# TMC2130-Eval_v13.net
KiCad netlist of a schematic drawn in EAGLE
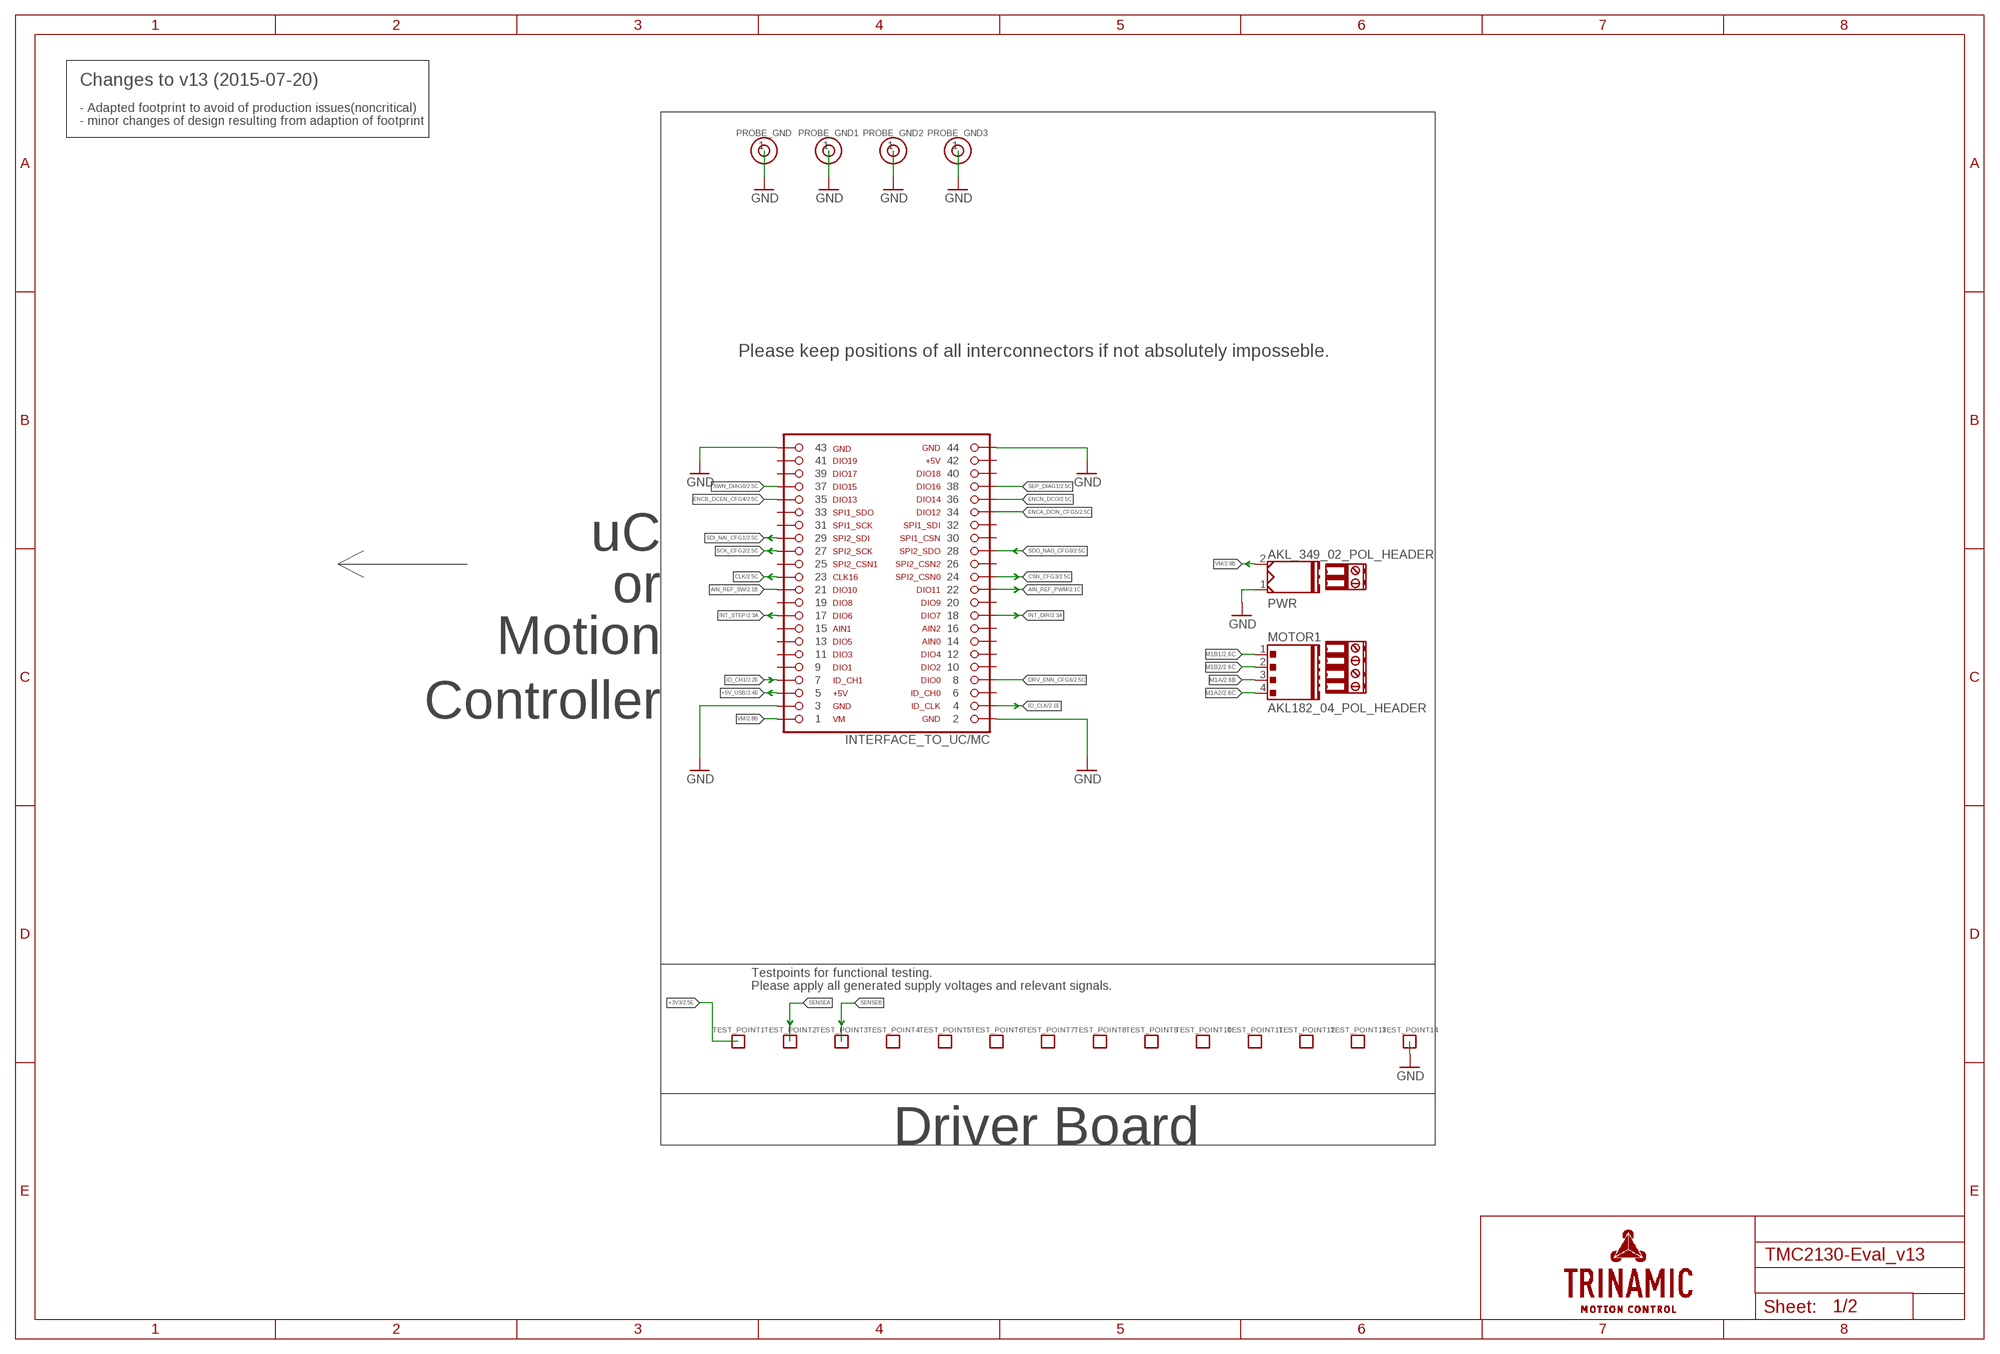
[diagram p0: schematic, sheet 1]
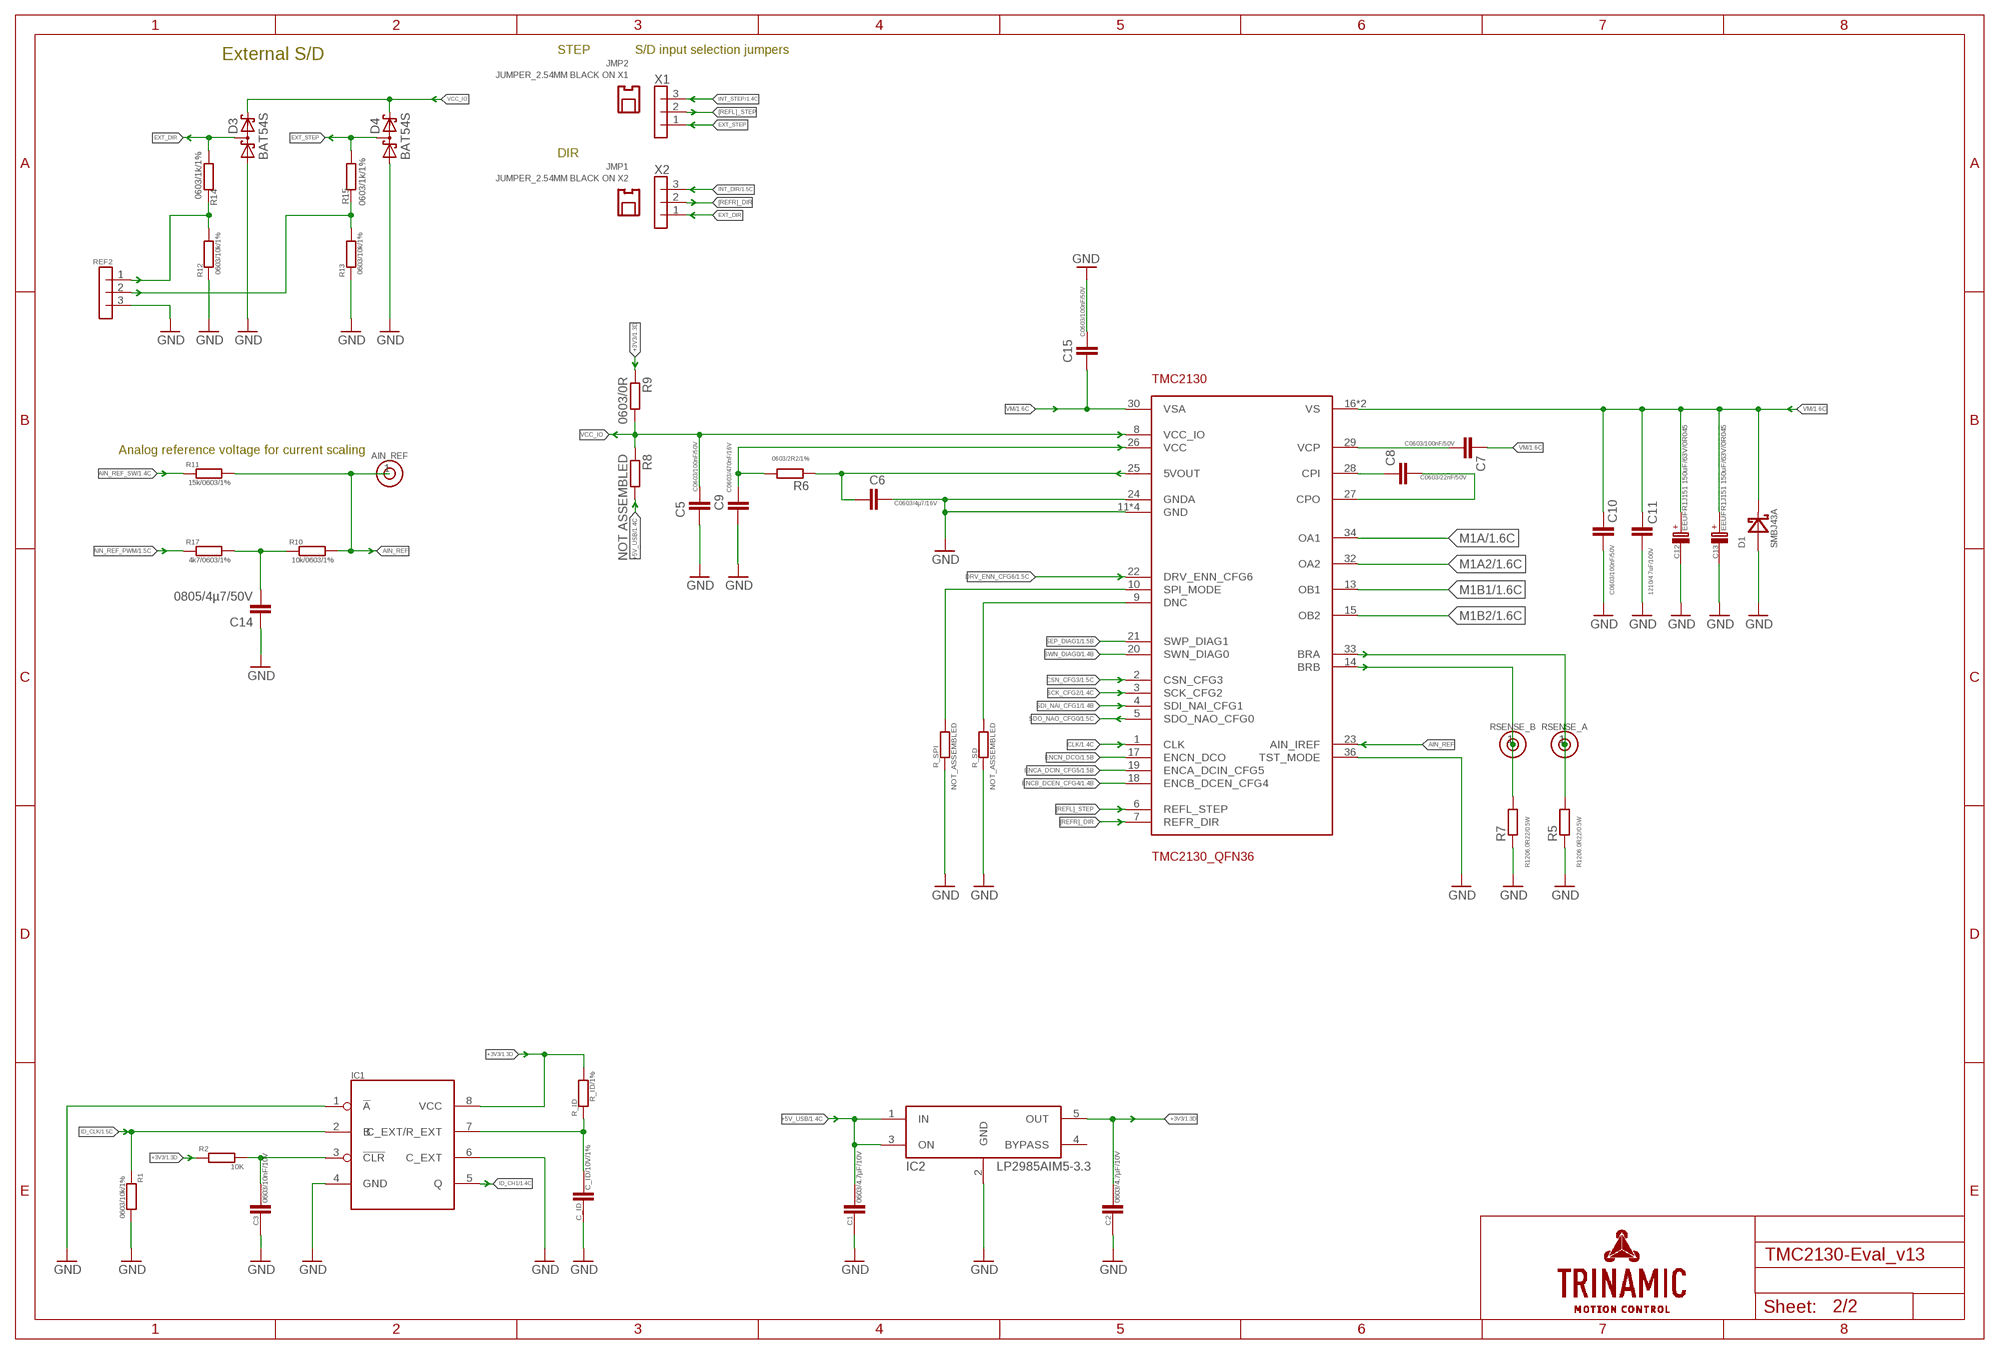
[diagram p1: schematic, sheet 2]

(export (version "E")
  (design (tool "Eeschema 10.0.6"))
  (components
    (comp (ref "INTERFACE_TO_UC/MC")
      (value "FEMALE_HEADER_SMD_2.54_44_PINSHORTPADS_HOLES")
      (footprint "eagle-import:FEMALE_HEADER_SMD_254_44_PIN_SHORTPADS_HOLES")
      (fields
        (field (name "1_PARTNUMBER") "098-3-044-1-NFX-YT0  ")
        (field (name "2_PARTNUMBER") "HLE-122-02-F-DV-A")
        (field (name "2_PARTNUMBER_1") "HLE-122-02-F-DV-A")
      )
      (libsource (lib "eagle-import") (part "FEMALE_HEADER_SMD_2.54_44_PINSHORTPADS_HOLES"))
    )
    (comp (ref "MOTOR1")
      (value "AKL182_04_POL_HEADER")
      (footprint "eagle-import:AKL169_04_POL")
      (fields (field (name "1_PARTNUMBER") "31182104") (field (name "2_PARTNUMBER") "AKL 182-04"))
      (libsource (lib "eagle-import") (part "AKL182_04_POL_HEADER"))
    )
    (comp (ref "PROBE_GND")
      (value "NOT ASSEMBLED")
      (footprint "eagle-import:1PIN_1ROW_THT")
      (libsource (lib "eagle-import") (part "1PIN_1ROW"))
    )
    (comp (ref "PROBE_GND1")
      (value "NOT ASSEMBLED")
      (footprint "eagle-import:1PIN_1ROW_THT")
      (libsource (lib "eagle-import") (part "1PIN_1ROW"))
    )
    (comp (ref "PROBE_GND2")
      (value "NOT ASSEMBLED")
      (footprint "eagle-import:1PIN_1ROW_THT")
      (libsource (lib "eagle-import") (part "1PIN_1ROW"))
    )
    (comp (ref "PROBE_GND3")
      (value "NOT ASSEMBLED")
      (footprint "eagle-import:1PIN_1ROW_THT")
      (libsource (lib "eagle-import") (part "1PIN_1ROW"))
    )
    (comp (ref "PWR")
      (value "AKL_349_02_POL_HEADER")
      (footprint "eagle-import:AKL349_02_POL")
      (fields (field (name "1_PARTNUMBER") "31330102") (field (name "2_PARTNUMBER") "AKL 330-02"))
      (libsource (lib "eagle-import") (part "AKL_349_02_POL_HEADER"))
    )
    (comp (ref "TERM1")
      (value "AKL_330_2_POL_TERMINAL")
      (footprint "eagle-import:EXTRA_TERMINAL")
      (fields (field (name "1_PARTNUMBER") "31349102") (field (name "2_PARTNUMBER") "AKL 349-02"))
      (libsource (lib "eagle-import") (part "AKL_330_2_POL_TERMINAL"))
    )
    (comp (ref "TERM2")
      (value "AKL182_04_POL_TERMINAL")
      (footprint "eagle-import:EXTRA_TERMINAL")
      (fields (field (name "1_PARTNUMBER") "31169104") (field (name "2_PARTNUMBER") "AKL 169-04"))
      (libsource (lib "eagle-import") (part "AKL182_04_POL_TERMINAL"))
    )
    (comp (ref "TEST_POINT1")
      (value "NOT ASSEMBLED")
      (footprint "eagle-import:PAD_R1.2")
      (libsource (lib "eagle-import") (part "PAD_ROUND"))
    )
    (comp (ref "TEST_POINT2")
      (value "NOT ASSEMBLED")
      (footprint "eagle-import:PAD_R1.2")
      (libsource (lib "eagle-import") (part "PAD_ROUND"))
    )
    (comp (ref "TEST_POINT3")
      (value "NOT ASSEMBLED")
      (footprint "eagle-import:PAD_R1.2")
      (libsource (lib "eagle-import") (part "PAD_ROUND"))
    )
    (comp (ref "TEST_POINT4")
      (value "NOT ASSEMBLED")
      (footprint "eagle-import:PAD_R1.2")
      (libsource (lib "eagle-import") (part "PAD_ROUND"))
    )
    (comp (ref "TEST_POINT5")
      (value "NOT ASSEMBLED")
      (footprint "eagle-import:PAD_R1.2")
      (libsource (lib "eagle-import") (part "PAD_ROUND"))
    )
    (comp (ref "TEST_POINT6")
      (value "NOT ASSEMBLED")
      (footprint "eagle-import:PAD_R1.2")
      (libsource (lib "eagle-import") (part "PAD_ROUND"))
    )
    (comp (ref "TEST_POINT7")
      (value "NOT ASSEMBLED")
      (footprint "eagle-import:PAD_R1.2")
      (libsource (lib "eagle-import") (part "PAD_ROUND"))
    )
    (comp (ref "TEST_POINT8")
      (value "NOT ASSEMBLED")
      (footprint "eagle-import:PAD_R1.2")
      (libsource (lib "eagle-import") (part "PAD_ROUND"))
    )
    (comp (ref "TEST_POINT9")
      (value "NOT ASSEMBLED")
      (footprint "eagle-import:PAD_R1.2")
      (libsource (lib "eagle-import") (part "PAD_ROUND"))
    )
    (comp (ref "TEST_POINT10")
      (value "NOT ASSEMBLED")
      (footprint "eagle-import:PAD_R1.2")
      (libsource (lib "eagle-import") (part "PAD_ROUND"))
    )
    (comp (ref "TEST_POINT11")
      (value "NOT ASSEMBLED")
      (footprint "eagle-import:PAD_R1.2")
      (libsource (lib "eagle-import") (part "PAD_ROUND"))
    )
    (comp (ref "TEST_POINT12")
      (value "NOT ASSEMBLED")
      (footprint "eagle-import:PAD_R1.2")
      (libsource (lib "eagle-import") (part "PAD_ROUND"))
    )
    (comp (ref "TEST_POINT13")
      (value "NOT ASSEMBLED")
      (footprint "eagle-import:PAD_R1.2")
      (libsource (lib "eagle-import") (part "PAD_ROUND"))
    )
    (comp (ref "TEST_POINT14")
      (value "NOT ASSEMBLED")
      (footprint "eagle-import:PAD_R1.2")
      (libsource (lib "eagle-import") (part "PAD_ROUND"))
    )
    (comp (ref "AIN_REF")
      (value "NOT ASSEMBLED")
      (footprint "eagle-import:1PIN_1ROW_THT")
      (libsource (lib "eagle-import") (part "1PIN_1ROW"))
    )
    (comp (ref "C1")
      (value "0603/4.7µF/10V")
      (footprint "eagle-import:RCL_0603")
      (libsource (lib "eagle-import") (part "RCL_C/0603"))
    )
    (comp (ref "C2")
      (value "0603/4.7µF/10V")
      (footprint "eagle-import:RCL_0603")
      (libsource (lib "eagle-import") (part "RCL_C/0603"))
    )
    (comp (ref "C3")
      (value "0603/10nF/10V")
      (footprint "eagle-import:RCL_0603")
      (libsource (lib "eagle-import") (part "RCL_C/0603"))
    )
    (comp (ref "C5")
      (value "C0603/100nF/50V")
      (footprint "eagle-import:C0603")
      (libsource (lib "eagle-import") (part "C-EUC0603"))
    )
    (comp (ref "C6")
      (value "C0603/4µ7/16V")
      (footprint "eagle-import:C0603")
      (libsource (lib "eagle-import") (part "C-EUC0603"))
    )
    (comp (ref "C7")
      (value "C0603/100nF/50V")
      (footprint "eagle-import:C0603")
      (libsource (lib "eagle-import") (part "C-EUC0603"))
    )
    (comp (ref "C8")
      (value "C0603/22nF/50V")
      (footprint "eagle-import:C0603")
      (libsource (lib "eagle-import") (part "C-EUC0603"))
    )
    (comp (ref "C9")
      (value "C0603/470nF/16V")
      (footprint "eagle-import:C0603")
      (libsource (lib "eagle-import") (part "C-EUC0603"))
    )
    (comp (ref "C10")
      (value "C0603/100nF/50V")
      (footprint "eagle-import:C0603")
      (libsource (lib "eagle-import") (part "C-EUC0603"))
    )
    (comp (ref "C11")
      (value "1210/4.7uF/100V")
      (footprint "eagle-import:C1210")
      (libsource (lib "eagle-import") (part "C-EUC1210"))
    )
    (comp (ref "C12")
      (value "EEUFR1J151 150uF/63V/0R045")
      (footprint "eagle-import:C_POL_RAD_THT_5X10X12.5")
      (libsource (lib "eagle-import") (part "C_POL"))
    )
    (comp (ref "C13")
      (value "EEUFR1J151 150uF/63V/0R045")
      (footprint "eagle-import:C_POL_RAD_THT_5X10X12.5")
      (libsource (lib "eagle-import") (part "C_POL"))
    )
    (comp (ref "C14")
      (value "0805/4µ7/50V")
      (footprint "eagle-import:C0805")
      (libsource (lib "eagle-import") (part "C-EUC0805"))
    )
    (comp (ref "C15")
      (value "C0603/100nF/50V")
      (footprint "eagle-import:C0603")
      (libsource (lib "eagle-import") (part "C-EUC0603"))
    )
    (comp (ref "C_ID")
      (value "C_ID/10V/1%")
      (footprint "eagle-import:RCL_0603")
      (libsource (lib "eagle-import") (part "RCL_C/0603"))
    )
    (comp (ref "D1")
      (value "SMBJ43A")
      (footprint "eagle-import:SMB")
      (libsource (lib "eagle-import") (part "SMBJ"))
    )
    (comp (ref "D3")
      (value "BAT54S")
      (footprint "eagle-import:SOT23")
      (libsource (lib "eagle-import") (part "BAT54S"))
    )
    (comp (ref "D4")
      (value "BAT54S")
      (footprint "eagle-import:SOT23")
      (libsource (lib "eagle-import") (part "BAT54S"))
    )
    (comp (ref "IC1")
      (value "SN74LVC1G123DCTR")
      (footprint "eagle-import:SN74LVC1G123DCTR")
      (libsource (lib "eagle-import") (part "SN74LVC1G123DCTR"))
    )
    (comp (ref "IC2")
      (value "LP2985AIM5-3.3")
      (footprint "eagle-import:SOT23-5")
      (libsource (lib "eagle-import") (part "LP2985AIM5-3.3"))
    )
    (comp (ref "JMP1")
      (value "JUMPER_2.54MM BLACK ON X2")
      (footprint "eagle-import:EXTRA_TERMINAL")
      (libsource (lib "eagle-import") (part "JUMPER_2.54MM"))
    )
    (comp (ref "JMP2")
      (value "JUMPER_2.54MM BLACK ON X1")
      (footprint "eagle-import:EXTRA_TERMINAL")
      (libsource (lib "eagle-import") (part "JUMPER_2.54MM"))
    )
    (comp (ref "R1")
      (value "0603/10k/1%")
      (footprint "eagle-import:RCL_0603")
      (libsource (lib "eagle-import") (part "RCL_R/0603"))
    )
    (comp (ref "R2")
      (value "10K")
      (footprint "eagle-import:RCL_0603")
      (libsource (lib "eagle-import") (part "RCL_R/0603"))
    )
    (comp (ref "R5")
      (value "R1206,0R22/0.5W")
      (footprint "eagle-import:R1206")
      (libsource (lib "eagle-import") (part "R-EU_R1206"))
    )
    (comp (ref "R6")
      (value "0603/2R2/1%")
      (footprint "eagle-import:R0603")
      (libsource (lib "eagle-import") (part "R-EU_R0603"))
    )
    (comp (ref "R7")
      (value "R1206,0R22/0.5W")
      (footprint "eagle-import:R1206")
      (libsource (lib "eagle-import") (part "R-EU_R1206"))
    )
    (comp (ref "R8")
      (value "NOT ASSEMBLED")
      (footprint "eagle-import:R0603")
      (libsource (lib "eagle-import") (part "R-EU_R0603"))
    )
    (comp (ref "R9")
      (value "0603/0R")
      (footprint "eagle-import:R0603")
      (libsource (lib "eagle-import") (part "R-EU_R0603"))
    )
    (comp (ref "R10")
      (value "10k/0603/1%")
      (footprint "eagle-import:RCL_0603")
      (libsource (lib "eagle-import") (part "RCL_R/0603"))
    )
    (comp (ref "R11")
      (value "15k/0603/1%")
      (footprint "eagle-import:RCL_0603")
      (libsource (lib "eagle-import") (part "RCL_R/0603"))
    )
    (comp (ref "R12")
      (value "0603/10k/1%")
      (footprint "eagle-import:0603")
      (libsource (lib "eagle-import") (part "R/0603"))
    )
    (comp (ref "R13")
      (value "0603/10k/1%")
      (footprint "eagle-import:0603")
      (libsource (lib "eagle-import") (part "R/0603"))
    )
    (comp (ref "R14")
      (value "0603/1k/1%")
      (footprint "eagle-import:0603")
      (libsource (lib "eagle-import") (part "R/0603"))
    )
    (comp (ref "R15")
      (value "0603/1k/1%")
      (footprint "eagle-import:0603")
      (libsource (lib "eagle-import") (part "R/0603"))
    )
    (comp (ref "R17")
      (value "4k7/0603/1%")
      (footprint "eagle-import:RCL_0603")
      (libsource (lib "eagle-import") (part "RCL_R/0603"))
    )
    (comp (ref "REF2")
      (value "MALE HEADER 2.54")
      (footprint "eagle-import:3PIN_1ROW_2,54_THT")
      (libsource (lib "eagle-import") (part "3PIN_1ROWTHT"))
    )
    (comp (ref "RSENSE_A")
      (value "NOT ASSEMBLED")
      (footprint "eagle-import:1PIN_1ROW_THT")
      (libsource (lib "eagle-import") (part "1PIN_1ROW"))
    )
    (comp (ref "RSENSE_B")
      (value "NOT ASSEMBLED")
      (footprint "eagle-import:1PIN_1ROW_THT")
      (libsource (lib "eagle-import") (part "1PIN_1ROW"))
    )
    (comp (ref "R_ID")
      (value "R_ID/1%")
      (footprint "eagle-import:RCL_0603")
      (libsource (lib "eagle-import") (part "RCL_R/0603"))
    )
    (comp (ref "R_SD")
      (value "NOT_ASSEMBLED")
      (footprint "eagle-import:RCL_0603")
      (libsource (lib "eagle-import") (part "RCL_R/0603"))
    )
    (comp (ref "R_SPI")
      (value "NOT_ASSEMBLED")
      (footprint "eagle-import:RCL_0603")
      (libsource (lib "eagle-import") (part "RCL_R/0603"))
    )
    (comp (ref "TMC2130")
      (value "TMC2130_QFN36")
      (footprint "eagle-import:QFN36")
      (libsource (lib "eagle-import") (part "TMC2130_QFN36"))
    )
    (comp (ref "X1")
      (value "MALE HEADER 2.54")
      (footprint "eagle-import:3PIN_1ROW_2,54_THT")
      (libsource (lib "eagle-import") (part "3PIN_1ROWTHT"))
    )
    (comp (ref "X2")
      (value "MALE HEADER 2.54")
      (footprint "eagle-import:3PIN_1ROW_2,54_THT")
      (libsource (lib "eagle-import") (part "3PIN_1ROWTHT"))
    )
  )
  (nets
    (net (code "1") (name "+3V3") (class "Default")
      (node (ref "C2") (pin "1") (pinfunction "1_1") (pintype "passive"))
      (node (ref "IC1") (pin "8") (pinfunction "VCC_8") (pintype "bidirectional"))
      (node (ref "IC2") (pin "5") (pinfunction "OUT_5") (pintype "bidirectional"))
      (node (ref "R2") (pin "1") (pinfunction "1_1") (pintype "passive"))
      (node (ref "R9") (pin "1") (pinfunction "1_1") (pintype "passive"))
      (node (ref "R_ID") (pin "2") (pinfunction "2_2") (pintype "passive"))
      (node (ref "TEST_POINT1") (pin "P$1") (pinfunction "P$1_P$1") (pintype "bidirectional"))
    )
    (net (code "2") (name "+5V_USB") (class "Default")
      (node (ref "C1") (pin "1") (pinfunction "1_1") (pintype "passive"))
      (node (ref "IC2") (pin "1") (pinfunction "IN_1") (pintype "bidirectional"))
      (node (ref "IC2") (pin "3") (pinfunction "ON_3") (pintype "bidirectional"))
      (node (ref "INTERFACE_TO_UC/MC") (pin "5") (pinfunction "5_5") (pintype "passive"))
      (node (ref "R8") (pin "2") (pinfunction "2_2") (pintype "passive"))
    )
    (net (code "3") (name "AIN_REF") (class "Default")
      (node (ref "AIN_REF") (pin "1") (pinfunction "P$1_1") (pintype "bidirectional"))
      (node (ref "R10") (pin "2") (pinfunction "2_2") (pintype "passive"))
      (node (ref "R11") (pin "2") (pinfunction "2_2") (pintype "passive"))
      (node (ref "TMC2130") (pin "23") (pinfunction "AIN_IREF_23") (pintype "bidirectional"))
    )
    (net (code "4") (name "AIN_REF_PWM") (class "Default")
      (node (ref "INTERFACE_TO_UC/MC") (pin "22") (pinfunction "22_22") (pintype "passive"))
      (node (ref "R17") (pin "1") (pinfunction "1_1") (pintype "passive"))
    )
    (net (code "5") (name "AIN_REF_SW") (class "Default")
      (node (ref "INTERFACE_TO_UC/MC") (pin "21") (pinfunction "21_21") (pintype "passive"))
      (node (ref "R11") (pin "1") (pinfunction "1_1") (pintype "passive"))
    )
    (net (code "6") (name "CLK") (class "Default")
      (node (ref "INTERFACE_TO_UC/MC") (pin "23") (pinfunction "23_23") (pintype "passive"))
      (node (ref "TMC2130") (pin "1") (pinfunction "CLK_1") (pintype "bidirectional"))
    )
    (net (code "7") (name "CSN_CFG3") (class "Default")
      (node (ref "INTERFACE_TO_UC/MC") (pin "24") (pinfunction "24_24") (pintype "passive"))
      (node (ref "TMC2130") (pin "2") (pinfunction "CSN_CFG3_2") (pintype "bidirectional"))
    )
    (net (code "8") (name "DRV_ENN_CFG6") (class "Default")
      (node (ref "INTERFACE_TO_UC/MC") (pin "8") (pinfunction "8_8") (pintype "passive"))
      (node (ref "TMC2130") (pin "22") (pinfunction "DRV_ENN_CFG6_22") (pintype "bidirectional"))
    )
    (net (code "9") (name "ENCA_DCIN_CFG5") (class "Default")
      (node (ref "INTERFACE_TO_UC/MC") (pin "34") (pinfunction "34_34") (pintype "passive"))
      (node (ref "TMC2130") (pin "19") (pinfunction "ENCA_DCIN_CFG5_19") (pintype "bidirectional"))
    )
    (net (code "10") (name "ENCB_DCEN_CFG4") (class "Default")
      (node (ref "INTERFACE_TO_UC/MC") (pin "35") (pinfunction "35_35") (pintype "passive"))
      (node (ref "TMC2130") (pin "18") (pinfunction "ENCB_DCEN_CFG4_18") (pintype "bidirectional"))
    )
    (net (code "11") (name "ENCN_DCO") (class "Default")
      (node (ref "INTERFACE_TO_UC/MC") (pin "36") (pinfunction "36_36") (pintype "passive"))
      (node (ref "TMC2130") (pin "17") (pinfunction "ENCN_DCO_17") (pintype "bidirectional"))
    )
    (net (code "12") (name "EXT_DIR") (class "Default")
      (node (ref "D3") (pin "3") (pinfunction "C1A2_3") (pintype "passive"))
      (node (ref "R14") (pin "2") (pinfunction "2_2") (pintype "passive"))
      (node (ref "X2") (pin "1") (pinfunction "1_1") (pintype "bidirectional"))
    )
    (net (code "13") (name "EXT_STEP") (class "Default")
      (node (ref "D4") (pin "3") (pinfunction "C1A2_3") (pintype "passive"))
      (node (ref "R15") (pin "2") (pinfunction "2_2") (pintype "passive"))
      (node (ref "X1") (pin "1") (pinfunction "1_1") (pintype "bidirectional"))
    )
    (net (code "14") (name "GND") (class "Default")
      (node (ref "C1") (pin "2") (pinfunction "2_2") (pintype "passive"))
      (node (ref "C10") (pin "1") (pinfunction "1_1") (pintype "passive"))
      (node (ref "C11") (pin "2") (pinfunction "2_2") (pintype "passive"))
      (node (ref "C12") (pin "-") (pinfunction "-_-") (pintype "passive"))
      (node (ref "C13") (pin "-") (pinfunction "-_-") (pintype "passive"))
      (node (ref "C14") (pin "1") (pinfunction "1_1") (pintype "passive"))
      (node (ref "C15") (pin "1") (pinfunction "1_1") (pintype "passive"))
      (node (ref "C2") (pin "2") (pinfunction "2_2") (pintype "passive"))
      (node (ref "C3") (pin "2") (pinfunction "2_2") (pintype "passive"))
      (node (ref "C5") (pin "2") (pinfunction "2_2") (pintype "passive"))
      (node (ref "C6") (pin "2") (pinfunction "2_2") (pintype "passive"))
      (node (ref "C9") (pin "1") (pinfunction "1_1") (pintype "passive"))
      (node (ref "C_ID") (pin "2") (pinfunction "2_2") (pintype "passive"))
      (node (ref "D1") (pin "A") (pinfunction "A_A") (pintype "bidirectional"))
      (node (ref "D3") (pin "1") (pinfunction "A1_1") (pintype "passive"))
      (node (ref "D4") (pin "1") (pinfunction "A1_1") (pintype "passive"))
      (node (ref "IC1") (pin "1") (pinfunction "~{A}_1") (pintype "bidirectional"))
      (node (ref "IC1") (pin "4") (pinfunction "GND_4") (pintype "bidirectional"))
      (node (ref "IC1") (pin "6") (pinfunction "C_EXT_6") (pintype "bidirectional"))
      (node (ref "IC2") (pin "2") (pinfunction "GND_2") (pintype "bidirectional"))
      (node (ref "INTERFACE_TO_UC/MC") (pin "2") (pinfunction "2_2") (pintype "passive"))
      (node (ref "INTERFACE_TO_UC/MC") (pin "3") (pinfunction "3_3") (pintype "passive"))
      (node (ref "INTERFACE_TO_UC/MC") (pin "43") (pinfunction "43_43") (pintype "passive"))
      (node (ref "INTERFACE_TO_UC/MC") (pin "44") (pinfunction "44_44") (pintype "passive"))
      (node (ref "PROBE_GND") (pin "1") (pinfunction "P$1_1") (pintype "bidirectional"))
      (node (ref "PROBE_GND1") (pin "1") (pinfunction "P$1_1") (pintype "bidirectional"))
      (node (ref "PROBE_GND2") (pin "1") (pinfunction "P$1_1") (pintype "bidirectional"))
      (node (ref "PROBE_GND3") (pin "1") (pinfunction "P$1_1") (pintype "bidirectional"))
      (node (ref "PWR") (pin "1") (pinfunction "1_1") (pintype "bidirectional"))
      (node (ref "R1") (pin "2") (pinfunction "2_2") (pintype "passive"))
      (node (ref "R12") (pin "1") (pinfunction "1_1") (pintype "passive"))
      (node (ref "R13") (pin "1") (pinfunction "1_1") (pintype "passive"))
      (node (ref "R5") (pin "1") (pinfunction "1_1") (pintype "passive"))
      (node (ref "R7") (pin "1") (pinfunction "1_1") (pintype "passive"))
      (node (ref "REF2") (pin "3") (pinfunction "3_3") (pintype "bidirectional"))
      (node (ref "R_SD") (pin "1") (pinfunction "1_1") (pintype "passive"))
      (node (ref "R_SPI") (pin "1") (pinfunction "1_1") (pintype "passive"))
      (node (ref "TEST_POINT14") (pin "P$1") (pinfunction "P$1_P$1") (pintype "bidirectional"))
      (node (ref "TMC2130") (pin "11") (pinfunction "GND_11") (pintype "bidirectional"))
      (node (ref "TMC2130") (pin "12") (pinfunction "GND_12") (pintype "bidirectional"))
      (node (ref "TMC2130") (pin "24") (pinfunction "GNDA_24") (pintype "bidirectional"))
      (node (ref "TMC2130") (pin "35") (pinfunction "GND_35") (pintype "bidirectional"))
      (node (ref "TMC2130") (pin "36") (pinfunction "TST_MODE_36") (pintype "bidirectional"))
      (node (ref "TMC2130") (pin "GND_PAD") (pinfunction "GND_GND_PAD") (pintype "bidirectional"))
    )
    (net (code "15") (name "ID_CH1") (class "Default")
      (node (ref "IC1") (pin "5") (pinfunction "Q_5") (pintype "bidirectional"))
      (node (ref "INTERFACE_TO_UC/MC") (pin "7") (pinfunction "7_7") (pintype "passive"))
    )
    (net (code "16") (name "ID_CLK") (class "Default")
      (node (ref "IC1") (pin "2") (pinfunction "B_2") (pintype "bidirectional"))
      (node (ref "INTERFACE_TO_UC/MC") (pin "4") (pinfunction "4_4") (pintype "passive"))
      (node (ref "R1") (pin "1") (pinfunction "1_1") (pintype "passive"))
    )
    (net (code "17") (name "INT_DIR") (class "Default")
      (node (ref "INTERFACE_TO_UC/MC") (pin "18") (pinfunction "18_18") (pintype "passive"))
      (node (ref "X2") (pin "3") (pinfunction "3_3") (pintype "bidirectional"))
    )
    (net (code "18") (name "INT_STEP") (class "Default")
      (node (ref "INTERFACE_TO_UC/MC") (pin "17") (pinfunction "17_17") (pintype "passive"))
      (node (ref "X1") (pin "3") (pinfunction "3_3") (pintype "bidirectional"))
    )
    (net (code "19") (name "M1A") (class "Default")
      (node (ref "MOTOR1") (pin "3") (pinfunction "3_3") (pintype "bidirectional"))
      (node (ref "TMC2130") (pin "34") (pinfunction "OA1_34") (pintype "bidirectional"))
    )
    (net (code "20") (name "M1A2") (class "Default")
      (node (ref "MOTOR1") (pin "4") (pinfunction "4_4") (pintype "bidirectional"))
      (node (ref "TMC2130") (pin "32") (pinfunction "OA2_32") (pintype "bidirectional"))
    )
    (net (code "21") (name "M1B1") (class "Default")
      (node (ref "MOTOR1") (pin "1") (pinfunction "1_1") (pintype "bidirectional"))
      (node (ref "TMC2130") (pin "13") (pinfunction "OB1_13") (pintype "bidirectional"))
    )
    (net (code "22") (name "M1B2") (class "Default")
      (node (ref "MOTOR1") (pin "2") (pinfunction "2_2") (pintype "bidirectional"))
      (node (ref "TMC2130") (pin "15") (pinfunction "OB2_15") (pintype "bidirectional"))
    )
    (net (code "23") (name "Net-(C14-Pad2)") (class "Default")
      (node (ref "C14") (pin "2") (pinfunction "2_2") (pintype "passive"))
      (node (ref "R10") (pin "1") (pinfunction "1_1") (pintype "passive"))
      (node (ref "R17") (pin "2") (pinfunction "2_2") (pintype "passive"))
    )
    (net (code "24") (name "Net-(IC1-C_EXT{slash}R_EXT)") (class "Default")
      (node (ref "C_ID") (pin "1") (pinfunction "1_1") (pintype "passive"))
      (node (ref "IC1") (pin "7") (pinfunction "C_EXT/R_EXT_7") (pintype "bidirectional"))
      (node (ref "R_ID") (pin "1") (pinfunction "1_1") (pintype "passive"))
    )
    (net (code "25") (name "Net-(IC1-~{CLR})") (class "Default")
      (node (ref "C3") (pin "1") (pinfunction "1_1") (pintype "passive"))
      (node (ref "IC1") (pin "3") (pinfunction "~{CLR}_3") (pintype "bidirectional"))
      (node (ref "R2") (pin "2") (pinfunction "2_2") (pintype "passive"))
    )
    (net (code "26") (name "Net-(R12-Pad2)") (class "Default")
      (node (ref "R12") (pin "2") (pinfunction "2_2") (pintype "passive"))
      (node (ref "R14") (pin "1") (pinfunction "1_1") (pintype "passive"))
      (node (ref "REF2") (pin "1") (pinfunction "1_1") (pintype "bidirectional"))
    )
    (net (code "27") (name "Net-(R13-Pad2)") (class "Default")
      (node (ref "R13") (pin "2") (pinfunction "2_2") (pintype "passive"))
      (node (ref "R15") (pin "1") (pinfunction "1_1") (pintype "passive"))
      (node (ref "REF2") (pin "2") (pinfunction "2_2") (pintype "bidirectional"))
    )
    (net (code "28") (name "Net-(TMC2130-5VOUT)") (class "Default")
      (node (ref "C6") (pin "1") (pinfunction "1_1") (pintype "passive"))
      (node (ref "R6") (pin "1") (pinfunction "1_1") (pintype "passive"))
      (node (ref "TMC2130") (pin "25") (pinfunction "5VOUT_25") (pintype "bidirectional"))
    )
    (net (code "29") (name "Net-(TMC2130-CPI)") (class "Default")
      (node (ref "C8") (pin "1") (pinfunction "1_1") (pintype "passive"))
      (node (ref "TMC2130") (pin "28") (pinfunction "CPI_28") (pintype "bidirectional"))
    )
    (net (code "30") (name "Net-(TMC2130-CPO)") (class "Default")
      (node (ref "C8") (pin "2") (pinfunction "2_2") (pintype "passive"))
      (node (ref "TMC2130") (pin "27") (pinfunction "CPO_27") (pintype "bidirectional"))
    )
    (net (code "31") (name "Net-(TMC2130-DNC)") (class "Default")
      (node (ref "R_SD") (pin "2") (pinfunction "2_2") (pintype "passive"))
      (node (ref "TMC2130") (pin "9") (pinfunction "DNC_9") (pintype "bidirectional"))
    )
    (net (code "32") (name "Net-(TMC2130-SPI_MODE)") (class "Default")
      (node (ref "R_SPI") (pin "2") (pinfunction "2_2") (pintype "passive"))
      (node (ref "TMC2130") (pin "10") (pinfunction "SPI_MODE_10") (pintype "bidirectional"))
    )
    (net (code "33") (name "Net-(TMC2130-VCC)") (class "Default")
      (node (ref "C9") (pin "2") (pinfunction "2_2") (pintype "passive"))
      (node (ref "R6") (pin "2") (pinfunction "2_2") (pintype "passive"))
      (node (ref "TMC2130") (pin "26") (pinfunction "VCC_26") (pintype "bidirectional"))
    )
    (net (code "34") (name "Net-(TMC2130-VCP)") (class "Default")
      (node (ref "C7") (pin "2") (pinfunction "2_2") (pintype "passive"))
      (node (ref "TMC2130") (pin "29") (pinfunction "VCP_29") (pintype "bidirectional"))
    )
    (net (code "35") (name "SCK_CFG2") (class "Default")
      (node (ref "INTERFACE_TO_UC/MC") (pin "27") (pinfunction "27_27") (pintype "passive"))
      (node (ref "TMC2130") (pin "3") (pinfunction "SCK_CFG2_3") (pintype "bidirectional"))
    )
    (net (code "36") (name "SDI_NAI_CFG1") (class "Default")
      (node (ref "INTERFACE_TO_UC/MC") (pin "29") (pinfunction "29_29") (pintype "passive"))
      (node (ref "TMC2130") (pin "4") (pinfunction "SDI_NAI_CFG1_4") (pintype "bidirectional"))
    )
    (net (code "37") (name "SDO_NAO_CFG0") (class "Default")
      (node (ref "INTERFACE_TO_UC/MC") (pin "28") (pinfunction "28_28") (pintype "passive"))
      (node (ref "TMC2130") (pin "5") (pinfunction "SDO_NAO_CFG0_5") (pintype "bidirectional"))
    )
    (net (code "38") (name "SENSEA") (class "Default")
      (node (ref "R5") (pin "2") (pinfunction "2_2") (pintype "passive"))
      (node (ref "RSENSE_A") (pin "1") (pinfunction "P$1_1") (pintype "bidirectional"))
      (node (ref "TEST_POINT2") (pin "P$1") (pinfunction "P$1_P$1") (pintype "bidirectional"))
      (node (ref "TMC2130") (pin "33") (pinfunction "BRA_33") (pintype "bidirectional"))
    )
    (net (code "39") (name "SENSEB") (class "Default")
      (node (ref "R7") (pin "2") (pinfunction "2_2") (pintype "passive"))
      (node (ref "RSENSE_B") (pin "1") (pinfunction "P$1_1") (pintype "bidirectional"))
      (node (ref "TEST_POINT3") (pin "P$1") (pinfunction "P$1_P$1") (pintype "bidirectional"))
      (node (ref "TMC2130") (pin "14") (pinfunction "BRB_14") (pintype "bidirectional"))
    )
    (net (code "40") (name "SEP_DIAG1") (class "Default")
      (node (ref "INTERFACE_TO_UC/MC") (pin "38") (pinfunction "38_38") (pintype "passive"))
      (node (ref "TMC2130") (pin "21") (pinfunction "SWP_DIAG1_21") (pintype "bidirectional"))
    )
    (net (code "41") (name "SWN_DIAG0") (class "Default")
      (node (ref "INTERFACE_TO_UC/MC") (pin "37") (pinfunction "37_37") (pintype "passive"))
      (node (ref "TMC2130") (pin "20") (pinfunction "SWN_DIAG0_20") (pintype "bidirectional"))
    )
    (net (code "42") (name "VCC_IO") (class "Default")
      (node (ref "C5") (pin "1") (pinfunction "1_1") (pintype "passive"))
      (node (ref "D3") (pin "2") (pinfunction "C2_2") (pintype "passive"))
      (node (ref "D4") (pin "2") (pinfunction "C2_2") (pintype "passive"))
      (node (ref "R8") (pin "1") (pinfunction "1_1") (pintype "passive"))
      (node (ref "R9") (pin "2") (pinfunction "2_2") (pintype "passive"))
      (node (ref "TMC2130") (pin "8") (pinfunction "VCC_IO_8") (pintype "bidirectional"))
    )
    (net (code "43") (name "VM") (class "Default")
      (node (ref "C10") (pin "2") (pinfunction "2_2") (pintype "passive"))
      (node (ref "C11") (pin "1") (pinfunction "1_1") (pintype "passive"))
      (node (ref "C12") (pin "+") (pinfunction "+_+") (pintype "passive"))
      (node (ref "C13") (pin "+") (pinfunction "+_+") (pintype "passive"))
      (node (ref "C15") (pin "2") (pinfunction "2_2") (pintype "passive"))
      (node (ref "C7") (pin "1") (pinfunction "1_1") (pintype "passive"))
      (node (ref "D1") (pin "C") (pinfunction "C_C") (pintype "bidirectional"))
      (node (ref "INTERFACE_TO_UC/MC") (pin "1") (pinfunction "1_1") (pintype "passive"))
      (node (ref "PWR") (pin "2") (pinfunction "2_2") (pintype "bidirectional"))
      (node (ref "TMC2130") (pin "16") (pinfunction "VS_16") (pintype "bidirectional"))
      (node (ref "TMC2130") (pin "30") (pinfunction "VSA_30") (pintype "bidirectional"))
      (node (ref "TMC2130") (pin "31") (pinfunction "VS_31") (pintype "bidirectional"))
    )
    (net (code "44") (name "[REFL]_STEP") (class "Default")
      (node (ref "TMC2130") (pin "6") (pinfunction "REFL_STEP_6") (pintype "bidirectional"))
      (node (ref "X1") (pin "2") (pinfunction "2_2") (pintype "bidirectional"))
    )
    (net (code "45") (name "[REFR]_DIR") (class "Default")
      (node (ref "TMC2130") (pin "7") (pinfunction "REFR_DIR_7") (pintype "bidirectional"))
      (node (ref "X2") (pin "2") (pinfunction "2_2") (pintype "bidirectional"))
    )
    (net (code "46") (name "unconnected-(IC2-BYPASS-Pad4)") (class "Default")
      (node (ref "IC2") (pin "4") (pinfunction "BYPASS_4") (pintype "bidirectional"))
    )
    (net (code "47") (name "unconnected-(INTERFACE_TO_UC/MC-Pad6)") (class "Default")
      (node (ref "INTERFACE_TO_UC/MC") (pin "6") (pinfunction "6_6") (pintype "passive"))
    )
    (net (code "48") (name "unconnected-(INTERFACE_TO_UC/MC-Pad9)") (class "Default")
      (node (ref "INTERFACE_TO_UC/MC") (pin "9") (pinfunction "9_9") (pintype "passive"))
    )
    (net (code "49") (name "unconnected-(INTERFACE_TO_UC/MC-Pad10)") (class "Default")
      (node (ref "INTERFACE_TO_UC/MC") (pin "10") (pinfunction "10_10") (pintype "passive"))
    )
    (net (code "50") (name "unconnected-(INTERFACE_TO_UC/MC-Pad11)") (class "Default")
      (node (ref "INTERFACE_TO_UC/MC") (pin "11") (pinfunction "11_11") (pintype "passive"))
    )
    (net (code "51") (name "unconnected-(INTERFACE_TO_UC/MC-Pad12)") (class "Default")
      (node (ref "INTERFACE_TO_UC/MC") (pin "12") (pinfunction "12_12") (pintype "passive"))
    )
    (net (code "52") (name "unconnected-(INTERFACE_TO_UC/MC-Pad13)") (class "Default")
      (node (ref "INTERFACE_TO_UC/MC") (pin "13") (pinfunction "13_13") (pintype "passive"))
    )
    (net (code "53") (name "unconnected-(INTERFACE_TO_UC/MC-Pad14)") (class "Default")
      (node (ref "INTERFACE_TO_UC/MC") (pin "14") (pinfunction "14_14") (pintype "passive"))
    )
    (net (code "54") (name "unconnected-(INTERFACE_TO_UC/MC-Pad15)") (class "Default")
      (node (ref "INTERFACE_TO_UC/MC") (pin "15") (pinfunction "15_15") (pintype "passive"))
    )
    (net (code "55") (name "unconnected-(INTERFACE_TO_UC/MC-Pad16)") (class "Default")
      (node (ref "INTERFACE_TO_UC/MC") (pin "16") (pinfunction "16_16") (pintype "passive"))
    )
    (net (code "56") (name "unconnected-(INTERFACE_TO_UC/MC-Pad19)") (class "Default")
      (node (ref "INTERFACE_TO_UC/MC") (pin "19") (pinfunction "19_19") (pintype "passive"))
    )
    (net (code "57") (name "unconnected-(INTERFACE_TO_UC/MC-Pad20)") (class "Default")
      (node (ref "INTERFACE_TO_UC/MC") (pin "20") (pinfunction "20_20") (pintype "passive"))
    )
    (net (code "58") (name "unconnected-(INTERFACE_TO_UC/MC-Pad25)") (class "Default")
      (node (ref "INTERFACE_TO_UC/MC") (pin "25") (pinfunction "25_25") (pintype "passive"))
    )
    (net (code "59") (name "unconnected-(INTERFACE_TO_UC/MC-Pad26)") (class "Default")
      (node (ref "INTERFACE_TO_UC/MC") (pin "26") (pinfunction "26_26") (pintype "passive"))
    )
    (net (code "60") (name "unconnected-(INTERFACE_TO_UC/MC-Pad30)") (class "Default")
      (node (ref "INTERFACE_TO_UC/MC") (pin "30") (pinfunction "30_30") (pintype "passive"))
    )
    (net (code "61") (name "unconnected-(INTERFACE_TO_UC/MC-Pad31)") (class "Default")
      (node (ref "INTERFACE_TO_UC/MC") (pin "31") (pinfunction "31_31") (pintype "passive"))
    )
    (net (code "62") (name "unconnected-(INTERFACE_TO_UC/MC-Pad32)") (class "Default")
      (node (ref "INTERFACE_TO_UC/MC") (pin "32") (pinfunction "32_32") (pintype "passive"))
    )
    (net (code "63") (name "unconnected-(INTERFACE_TO_UC/MC-Pad33)") (class "Default")
      (node (ref "INTERFACE_TO_UC/MC") (pin "33") (pinfunction "33_33") (pintype "passive"))
    )
    (net (code "64") (name "unconnected-(INTERFACE_TO_UC/MC-Pad39)") (class "Default")
      (node (ref "INTERFACE_TO_UC/MC") (pin "39") (pinfunction "39_39") (pintype "passive"))
    )
    (net (code "65") (name "unconnected-(INTERFACE_TO_UC/MC-Pad40)") (class "Default")
      (node (ref "INTERFACE_TO_UC/MC") (pin "40") (pinfunction "40_40") (pintype "passive"))
    )
    (net (code "66") (name "unconnected-(INTERFACE_TO_UC/MC-Pad41)") (class "Default")
      (node (ref "INTERFACE_TO_UC/MC") (pin "41") (pinfunction "41_41") (pintype "passive"))
    )
    (net (code "67") (name "unconnected-(INTERFACE_TO_UC/MC-Pad42)") (class "Default")
      (node (ref "INTERFACE_TO_UC/MC") (pin "42") (pinfunction "42_42") (pintype "passive"))
    )
    (net (code "68") (name "unconnected-(TEST_POINT4-PadP$1)") (class "Default")
      (node (ref "TEST_POINT4") (pin "P$1") (pinfunction "P$1_P$1") (pintype "bidirectional"))
    )
    (net (code "69") (name "unconnected-(TEST_POINT5-PadP$1)") (class "Default")
      (node (ref "TEST_POINT5") (pin "P$1") (pinfunction "P$1_P$1") (pintype "bidirectional"))
    )
    (net (code "70") (name "unconnected-(TEST_POINT6-PadP$1)") (class "Default")
      (node (ref "TEST_POINT6") (pin "P$1") (pinfunction "P$1_P$1") (pintype "bidirectional"))
    )
    (net (code "71") (name "unconnected-(TEST_POINT7-PadP$1)") (class "Default")
      (node (ref "TEST_POINT7") (pin "P$1") (pinfunction "P$1_P$1") (pintype "bidirectional"))
    )
    (net (code "72") (name "unconnected-(TEST_POINT8-PadP$1)") (class "Default")
      (node (ref "TEST_POINT8") (pin "P$1") (pinfunction "P$1_P$1") (pintype "bidirectional"))
    )
    (net (code "73") (name "unconnected-(TEST_POINT9-PadP$1)") (class "Default")
      (node (ref "TEST_POINT9") (pin "P$1") (pinfunction "P$1_P$1") (pintype "bidirectional"))
    )
    (net (code "74") (name "unconnected-(TEST_POINT10-PadP$1)") (class "Default")
      (node (ref "TEST_POINT10") (pin "P$1") (pinfunction "P$1_P$1") (pintype "bidirectional"))
    )
    (net (code "75") (name "unconnected-(TEST_POINT11-PadP$1)") (class "Default")
      (node (ref "TEST_POINT11") (pin "P$1") (pinfunction "P$1_P$1") (pintype "bidirectional"))
    )
    (net (code "76") (name "unconnected-(TEST_POINT12-PadP$1)") (class "Default")
      (node (ref "TEST_POINT12") (pin "P$1") (pinfunction "P$1_P$1") (pintype "bidirectional"))
    )
    (net (code "77") (name "unconnected-(TEST_POINT13-PadP$1)") (class "Default")
      (node (ref "TEST_POINT13") (pin "P$1") (pinfunction "P$1_P$1") (pintype "bidirectional"))
    )
  )
)
